# Disp.net
KiCad netlist of a schematic drawn in Altium Designer
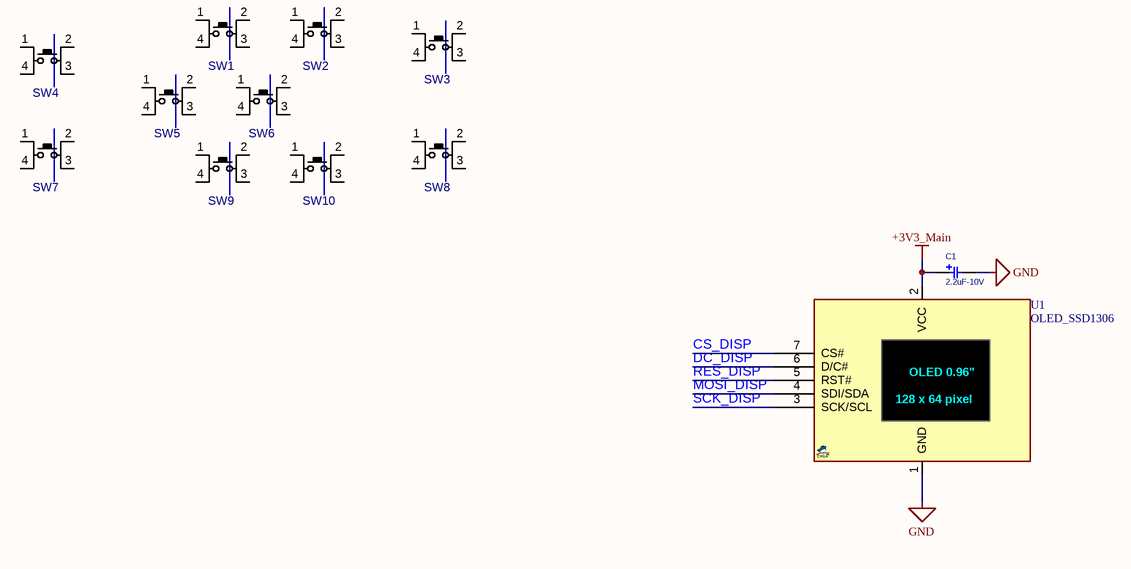
[diagram p0: Disp.SchDoc]

(export (version "E")
  (design (tool "Eeschema 10.0.6"))
  (components
    (comp (ref "C1")
      (value "2.2uF-10V")
      (footprint "C_TN_3216")
      (description "CAP, SMD, TAN,")
      (libsource (lib "passive_smd") (part "CAP_SMD_TAN"))
    )
    (comp (ref "SW1")
      (value "PUSHBUTTON")
      (footprint "SWPBS_SPDT_6X6X4")
      (description "SWITCH, PUSH BUTTON, TACTILE, SMD, SPDT, 6X6X4.3mm")
      (fields (field (name "MANF") "Bond-Tact") (field (name "MANF_P#") "TS-1143S"))
      (libsource (lib "switch_tact_PUSHB") (part "SWPBS_SPDT_6X6X4"))
    )
    (comp (ref "SW2")
      (value "PUSHBUTTON")
      (footprint "SWPBS_SPDT_6X6X4")
      (description "SWITCH, PUSH BUTTON, TACTILE, SMD, SPDT, 6X6X4.3mm")
      (fields (field (name "MANF") "Bond-Tact") (field (name "MANF_P#") "TS-1143S"))
      (libsource (lib "switch_tact_PUSHB") (part "SWPBS_SPDT_6X6X4"))
    )
    (comp (ref "SW3")
      (value "PUSHBUTTON")
      (footprint "SWPBS_SPDT_6X6X4")
      (description "SWITCH, PUSH BUTTON, TACTILE, SMD, SPDT, 6X6X4.3mm")
      (fields (field (name "MANF") "Bond-Tact") (field (name "MANF_P#") "TS-1143S"))
      (libsource (lib "switch_tact_PUSHB") (part "SWPBS_SPDT_6X6X4"))
    )
    (comp (ref "SW4")
      (value "PUSHBUTTON")
      (footprint "SWPBS_SPDT_3X3TS")
      (description "SWITCH, PUSH BUTTON, TACTILE, SMD, SPDT, 3X3MM")
      (fields (field (name "MANF") "CHINA") (field (name "MANF_P#") "TS-1233"))
      (libsource (lib "switch_tact_PUSHB") (part "SWPBS_SPDT_3X3TS"))
    )
    (comp (ref "SW5")
      (value "PUSHBUTTON")
      (footprint "SWPBS_SPDT_6X6X4")
      (description "SWITCH, PUSH BUTTON, TACTILE, SMD, SPDT, 6X6X4.3mm")
      (fields (field (name "MANF") "Bond-Tact") (field (name "MANF_P#") "TS-1143S"))
      (libsource (lib "switch_tact_PUSHB") (part "SWPBS_SPDT_6X6X4"))
    )
    (comp (ref "SW6")
      (value "PUSHBUTTON")
      (footprint "SWPBS_SPDT_6X6X4")
      (description "SWITCH, PUSH BUTTON, TACTILE, SMD, SPDT, 6X6X4.3mm")
      (fields (field (name "MANF") "Bond-Tact") (field (name "MANF_P#") "TS-1143S"))
      (libsource (lib "switch_tact_PUSHB") (part "SWPBS_SPDT_6X6X4"))
    )
    (comp (ref "SW7")
      (value "PUSHBUTTON")
      (footprint "SWPBS_SPDT_3X3TS")
      (description "SWITCH, PUSH BUTTON, TACTILE, SMD, SPDT, 3X3MM")
      (fields (field (name "MANF") "CHINA") (field (name "MANF_P#") "TS-1233"))
      (libsource (lib "switch_tact_PUSHB") (part "SWPBS_SPDT_3X3TS"))
    )
    (comp (ref "SW8")
      (value "PUSHBUTTON")
      (footprint "SWPBS_SPDT_6X6X4")
      (description "SWITCH, PUSH BUTTON, TACTILE, SMD, SPDT, 6X6X4.3mm")
      (fields (field (name "MANF") "Bond-Tact") (field (name "MANF_P#") "TS-1143S"))
      (libsource (lib "switch_tact_PUSHB") (part "SWPBS_SPDT_6X6X4"))
    )
    (comp (ref "SW9")
      (value "PUSHBUTTON")
      (footprint "SWPBS_SPDT_6X6X4")
      (description "SWITCH, PUSH BUTTON, TACTILE, SMD, SPDT, 6X6X4.3mm")
      (fields (field (name "MANF") "Bond-Tact") (field (name "MANF_P#") "TS-1143S"))
      (libsource (lib "switch_tact_PUSHB") (part "SWPBS_SPDT_6X6X4"))
    )
    (comp (ref "SW10")
      (value "PUSHBUTTON")
      (footprint "SWPBS_SPDT_6X6X4")
      (description "SWITCH, PUSH BUTTON, TACTILE, SMD, SPDT, 6X6X4.3mm")
      (fields (field (name "MANF") "Bond-Tact") (field (name "MANF_P#") "TS-1143S"))
      (libsource (lib "switch_tact_PUSHB") (part "SWPBS_SPDT_6X6X4"))
    )
    (comp (ref "U1")
      (value "OLED_SSD1306")
      (footprint "OLED_SSD1306_64_SPI")
      (description "OLED, SSD1306, 0.96\", 128X64, BREAKOUT SPI")
      (fields (field (name "MANF_P#") "OLED_SSD1306_I2C"))
      (libsource (lib "oled") (part "OLED_SSD1306_64_SPI"))
    )
  )
  (nets
    (net (code "1") (name "+3V3_Main") (class "Default")
      (node (ref "C1") (pin "1") (pinfunction "1_1") (pintype "passive"))
      (node (ref "U1") (pin "2") (pinfunction "VCC_2") (pintype "passive"))
    )
    (net (code "2") (name "/CS_DISP") (class "Default")
      (node (ref "U1") (pin "7") (pinfunction "CS#_7") (pintype "passive"))
    )
    (net (code "3") (name "/DC_DISP") (class "Default")
      (node (ref "U1") (pin "6") (pinfunction "D/C#_6") (pintype "passive"))
    )
    (net (code "4") (name "/MOSI_DISP") (class "Default")
      (node (ref "U1") (pin "4") (pinfunction "SDI/SDA_4") (pintype "passive"))
    )
    (net (code "5") (name "/RES_DISP") (class "Default")
      (node (ref "U1") (pin "5") (pinfunction "RST#_5") (pintype "passive"))
    )
    (net (code "6") (name "/SCK_DISP") (class "Default")
      (node (ref "U1") (pin "3") (pinfunction "SCK/SCL_3") (pintype "passive"))
    )
    (net (code "7") (name "GND") (class "Default")
      (node (ref "C1") (pin "2") (pinfunction "2_2") (pintype "passive"))
      (node (ref "U1") (pin "1") (pinfunction "GND_1") (pintype "passive"))
    )
    (net (code "8") (name "unconnected-(SW1-P1-Pad1)") (class "Default")
      (node (ref "SW1") (pin "1") (pinfunction "P1_1") (pintype "passive"))
    )
    (net (code "9") (name "unconnected-(SW1-P2-Pad4)") (class "Default")
      (node (ref "SW1") (pin "4") (pinfunction "P2_4") (pintype "passive"))
    )
    (net (code "10") (name "unconnected-(SW1-P3-Pad2)") (class "Default")
      (node (ref "SW1") (pin "2") (pinfunction "P3_2") (pintype "passive"))
    )
    (net (code "11") (name "unconnected-(SW1-P4-Pad3)") (class "Default")
      (node (ref "SW1") (pin "3") (pinfunction "P4_3") (pintype "passive"))
    )
    (net (code "12") (name "unconnected-(SW2-P1-Pad1)") (class "Default")
      (node (ref "SW2") (pin "1") (pinfunction "P1_1") (pintype "passive"))
    )
    (net (code "13") (name "unconnected-(SW2-P2-Pad4)") (class "Default")
      (node (ref "SW2") (pin "4") (pinfunction "P2_4") (pintype "passive"))
    )
    (net (code "14") (name "unconnected-(SW2-P3-Pad2)") (class "Default")
      (node (ref "SW2") (pin "2") (pinfunction "P3_2") (pintype "passive"))
    )
    (net (code "15") (name "unconnected-(SW2-P4-Pad3)") (class "Default")
      (node (ref "SW2") (pin "3") (pinfunction "P4_3") (pintype "passive"))
    )
    (net (code "16") (name "unconnected-(SW3-P1-Pad1)") (class "Default")
      (node (ref "SW3") (pin "1") (pinfunction "P1_1") (pintype "passive"))
    )
    (net (code "17") (name "unconnected-(SW3-P2-Pad4)") (class "Default")
      (node (ref "SW3") (pin "4") (pinfunction "P2_4") (pintype "passive"))
    )
    (net (code "18") (name "unconnected-(SW3-P3-Pad2)") (class "Default")
      (node (ref "SW3") (pin "2") (pinfunction "P3_2") (pintype "passive"))
    )
    (net (code "19") (name "unconnected-(SW3-P4-Pad3)") (class "Default")
      (node (ref "SW3") (pin "3") (pinfunction "P4_3") (pintype "passive"))
    )
    (net (code "20") (name "unconnected-(SW4-P1-Pad1)") (class "Default")
      (node (ref "SW4") (pin "1") (pinfunction "P1_1") (pintype "passive"))
    )
    (net (code "21") (name "unconnected-(SW4-P2-Pad4)") (class "Default")
      (node (ref "SW4") (pin "4") (pinfunction "P2_4") (pintype "passive"))
    )
    (net (code "22") (name "unconnected-(SW4-P3-Pad2)") (class "Default")
      (node (ref "SW4") (pin "2") (pinfunction "P3_2") (pintype "passive"))
    )
    (net (code "23") (name "unconnected-(SW4-P4-Pad3)") (class "Default")
      (node (ref "SW4") (pin "3") (pinfunction "P4_3") (pintype "passive"))
    )
    (net (code "24") (name "unconnected-(SW5-P1-Pad1)") (class "Default")
      (node (ref "SW5") (pin "1") (pinfunction "P1_1") (pintype "passive"))
    )
    (net (code "25") (name "unconnected-(SW5-P2-Pad4)") (class "Default")
      (node (ref "SW5") (pin "4") (pinfunction "P2_4") (pintype "passive"))
    )
    (net (code "26") (name "unconnected-(SW5-P3-Pad2)") (class "Default")
      (node (ref "SW5") (pin "2") (pinfunction "P3_2") (pintype "passive"))
    )
    (net (code "27") (name "unconnected-(SW5-P4-Pad3)") (class "Default")
      (node (ref "SW5") (pin "3") (pinfunction "P4_3") (pintype "passive"))
    )
    (net (code "28") (name "unconnected-(SW6-P1-Pad1)") (class "Default")
      (node (ref "SW6") (pin "1") (pinfunction "P1_1") (pintype "passive"))
    )
    (net (code "29") (name "unconnected-(SW6-P2-Pad4)") (class "Default")
      (node (ref "SW6") (pin "4") (pinfunction "P2_4") (pintype "passive"))
    )
    (net (code "30") (name "unconnected-(SW6-P3-Pad2)") (class "Default")
      (node (ref "SW6") (pin "2") (pinfunction "P3_2") (pintype "passive"))
    )
    (net (code "31") (name "unconnected-(SW6-P4-Pad3)") (class "Default")
      (node (ref "SW6") (pin "3") (pinfunction "P4_3") (pintype "passive"))
    )
    (net (code "32") (name "unconnected-(SW7-P1-Pad1)") (class "Default")
      (node (ref "SW7") (pin "1") (pinfunction "P1_1") (pintype "passive"))
    )
    (net (code "33") (name "unconnected-(SW7-P2-Pad4)") (class "Default")
      (node (ref "SW7") (pin "4") (pinfunction "P2_4") (pintype "passive"))
    )
    (net (code "34") (name "unconnected-(SW7-P3-Pad2)") (class "Default")
      (node (ref "SW7") (pin "2") (pinfunction "P3_2") (pintype "passive"))
    )
    (net (code "35") (name "unconnected-(SW7-P4-Pad3)") (class "Default")
      (node (ref "SW7") (pin "3") (pinfunction "P4_3") (pintype "passive"))
    )
    (net (code "36") (name "unconnected-(SW8-P1-Pad1)") (class "Default")
      (node (ref "SW8") (pin "1") (pinfunction "P1_1") (pintype "passive"))
    )
    (net (code "37") (name "unconnected-(SW8-P2-Pad4)") (class "Default")
      (node (ref "SW8") (pin "4") (pinfunction "P2_4") (pintype "passive"))
    )
    (net (code "38") (name "unconnected-(SW8-P3-Pad2)") (class "Default")
      (node (ref "SW8") (pin "2") (pinfunction "P3_2") (pintype "passive"))
    )
    (net (code "39") (name "unconnected-(SW8-P4-Pad3)") (class "Default")
      (node (ref "SW8") (pin "3") (pinfunction "P4_3") (pintype "passive"))
    )
    (net (code "40") (name "unconnected-(SW9-P1-Pad1)") (class "Default")
      (node (ref "SW9") (pin "1") (pinfunction "P1_1") (pintype "passive"))
    )
    (net (code "41") (name "unconnected-(SW9-P2-Pad4)") (class "Default")
      (node (ref "SW9") (pin "4") (pinfunction "P2_4") (pintype "passive"))
    )
    (net (code "42") (name "unconnected-(SW9-P3-Pad2)") (class "Default")
      (node (ref "SW9") (pin "2") (pinfunction "P3_2") (pintype "passive"))
    )
    (net (code "43") (name "unconnected-(SW9-P4-Pad3)") (class "Default")
      (node (ref "SW9") (pin "3") (pinfunction "P4_3") (pintype "passive"))
    )
    (net (code "44") (name "unconnected-(SW10-P1-Pad1)") (class "Default")
      (node (ref "SW10") (pin "1") (pinfunction "P1_1") (pintype "passive"))
    )
    (net (code "45") (name "unconnected-(SW10-P2-Pad4)") (class "Default")
      (node (ref "SW10") (pin "4") (pinfunction "P2_4") (pintype "passive"))
    )
    (net (code "46") (name "unconnected-(SW10-P3-Pad2)") (class "Default")
      (node (ref "SW10") (pin "2") (pinfunction "P3_2") (pintype "passive"))
    )
    (net (code "47") (name "unconnected-(SW10-P4-Pad3)") (class "Default")
      (node (ref "SW10") (pin "3") (pinfunction "P4_3") (pintype "passive"))
    )
  )
)
